# 20_SwitchingRegulator_CH_C-D.net
KiCad netlist of a schematic drawn in Altium Designer
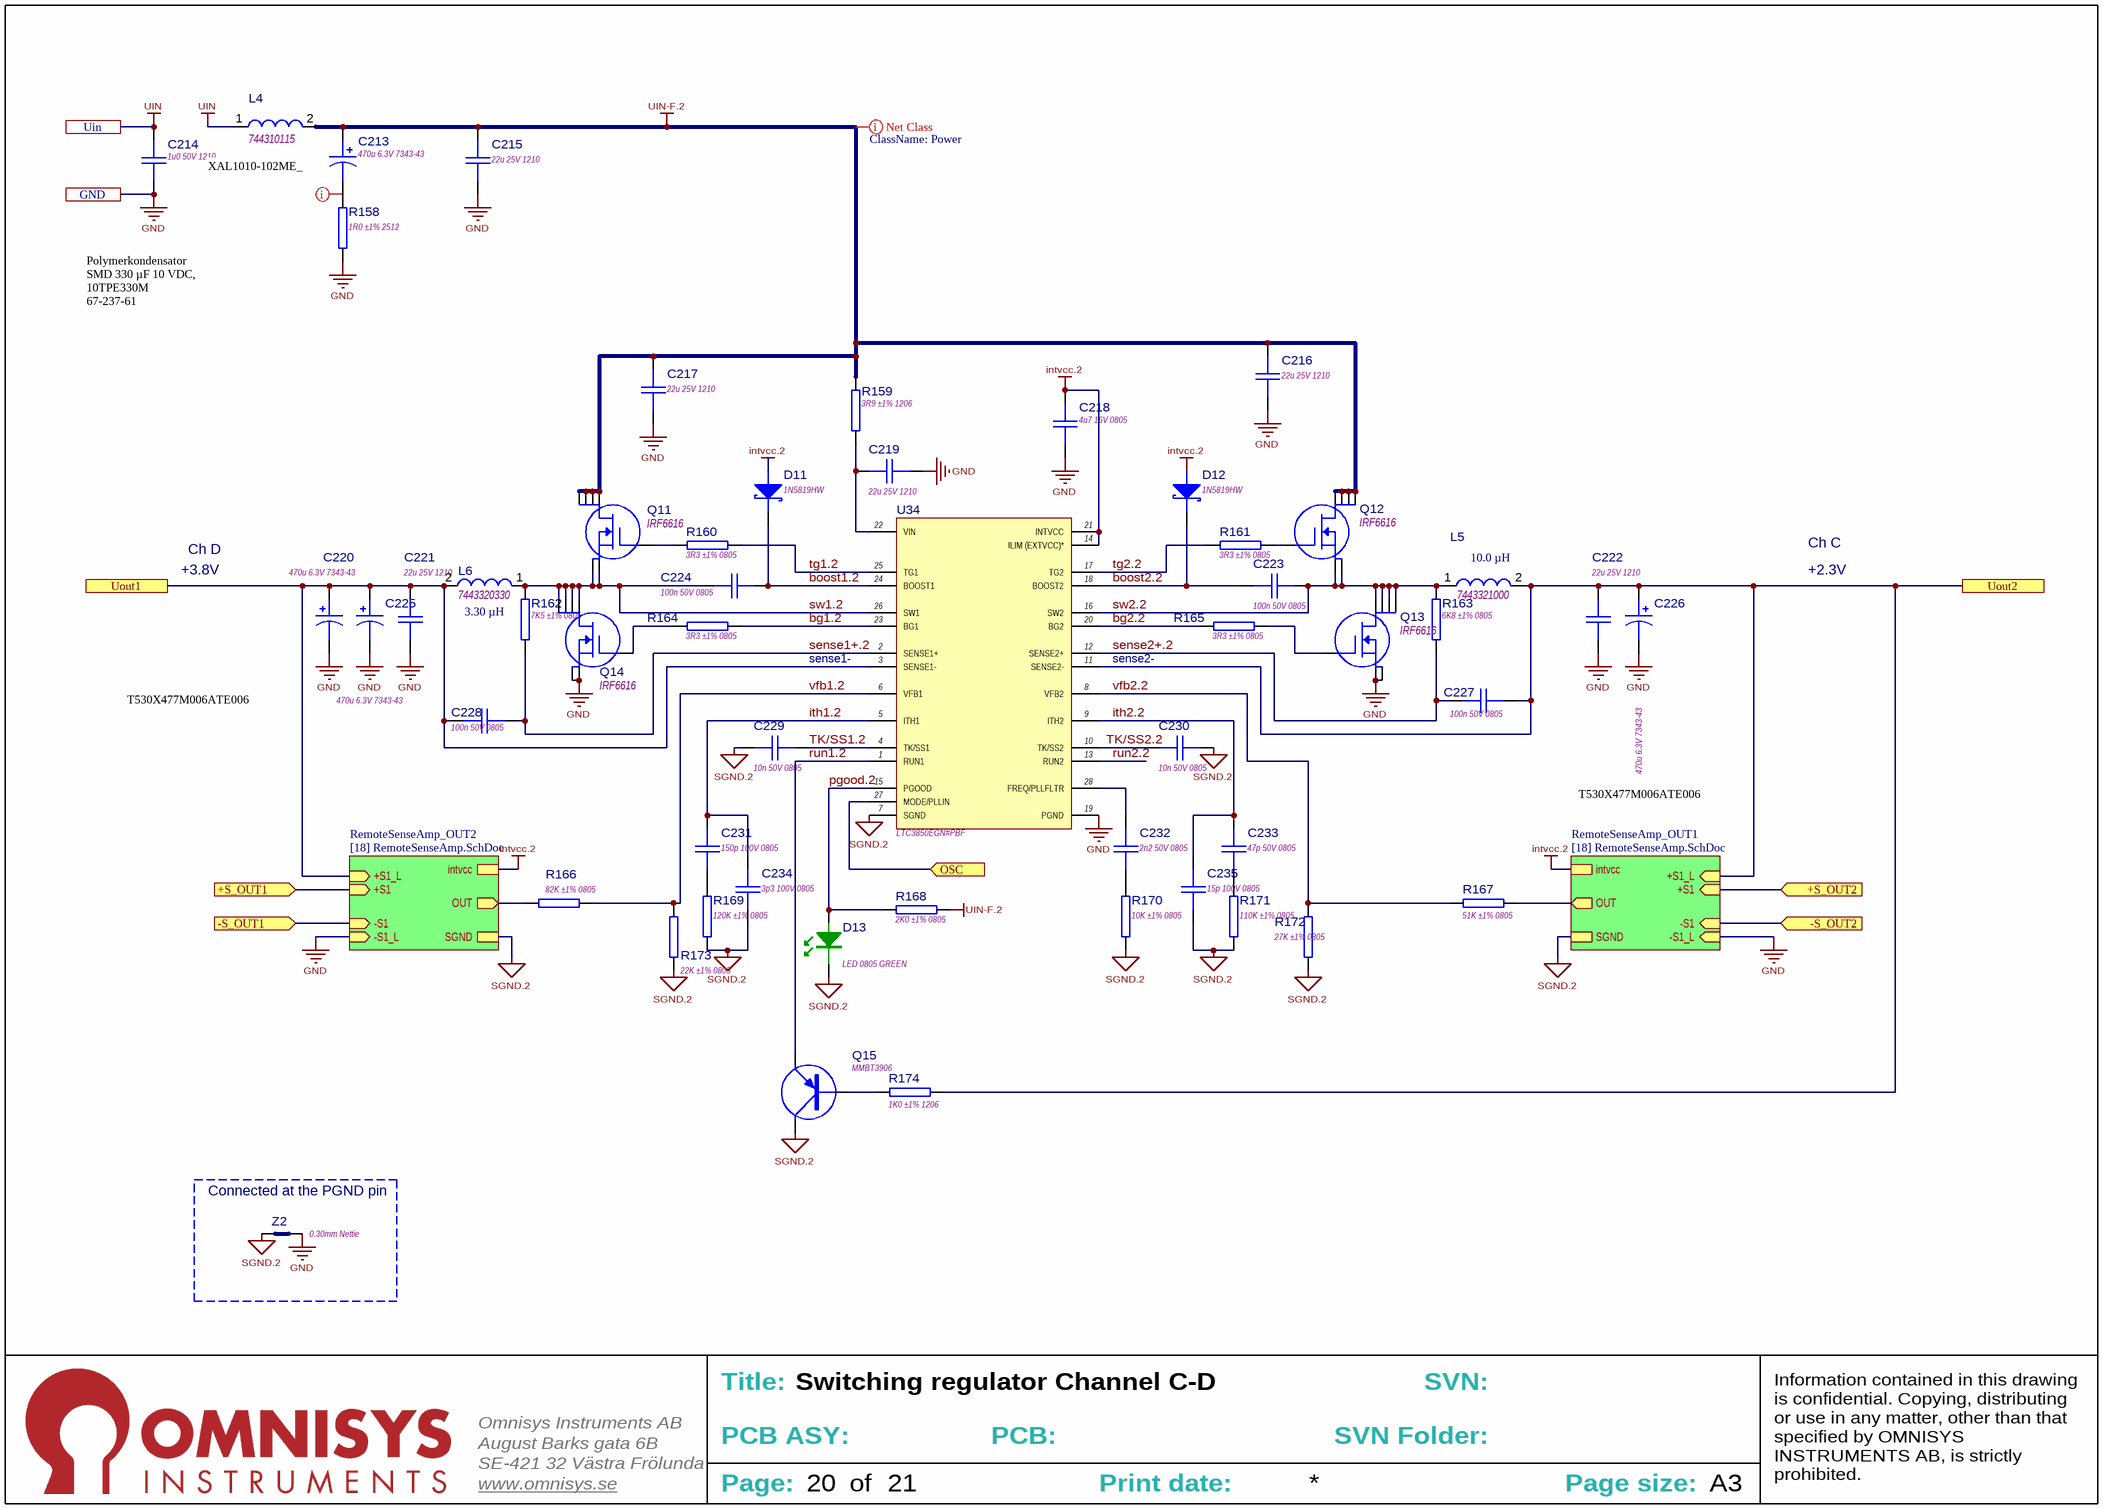
[diagram p0: [20] SwitchingRegulator CH C-D.SchDoc]

(export (version "E")
  (design (tool "Eeschema 10.0.6"))
  (components
    (comp (ref "C213")
      (value "470u 6.3V 7343-43")
      (footprint "CAPMP7343X43N")
      (description "Standard tantalum capacitor, 470u 6.3V 7343-43, Case E, TAJE477M006#NJ")
      (fields (field (name "TOLERANCE") "±20%"))
      (libsource (lib "") (part "CAP-2PIN-POL_1"))
    )
    (comp (ref "C214")
      (value "1u0 50V 1210")
      (footprint "CAPC3225X200N")
      (description "1u0 50V X7R ±10% 1210 (3225 metric)")
      (fields (field (name "TOLERANCE") "10%") (field (name "PARTNUMBER") "GRM32RR71H105KA01"))
      (libsource (lib "Omnisys Vault") (part "CAP-2PIN"))
    )
    (comp (ref "C215")
      (value "22u 25V 1210")
      (footprint "CAPC3225X270N")
      (description "22u 25V X7R ±10% 1210 (3225 metric)")
      (fields (field (name "TOLERANCE") "10%") (field (name "PARTNUMBER") "GRM32ER71E226ME15"))
      (libsource (lib "Omnisys Vault") (part "CAP-2PIN"))
    )
    (comp (ref "C216")
      (value "22u 25V 1210")
      (footprint "CAPC3225X270N")
      (description "22u 25V X7R ±10% 1210 (3225 metric)")
      (fields (field (name "TOLERANCE") "10%") (field (name "PARTNUMBER") "GRM32ER71E226ME15"))
      (libsource (lib "Omnisys Vault") (part "CAP-2PIN"))
    )
    (comp (ref "C217")
      (value "22u 25V 1210")
      (footprint "CAPC3225X270N")
      (description "22u 25V X7R ±10% 1210 (3225 metric)")
      (fields (field (name "TOLERANCE") "10%") (field (name "PARTNUMBER") "GRM32ER71E226ME15"))
      (libsource (lib "Omnisys Vault") (part "CAP-2PIN"))
    )
    (comp (ref "C218")
      (value "4u7 16V 0805")
      (footprint "CAPC2012X140N")
      (description "4u7 16V X7R ±10% 0805 (2012 metric)")
      (fields (field (name "TOLERANCE") "10%") (field (name "PARTNUMBER") "GRM21BR71C475KA73"))
      (libsource (lib "Omnisys Vault") (part "CAP-2PIN"))
    )
    (comp (ref "C219")
      (value "22u 25V 1210")
      (footprint "CAPC3225X270N")
      (description "22u 25V X7R ±10% 1210 (3225 metric)")
      (fields (field (name "TOLERANCE") "10%") (field (name "PARTNUMBER") "GRM32ER71E226ME15"))
      (libsource (lib "Omnisys Vault") (part "CAP-2PIN"))
    )
    (comp (ref "C220")
      (value "470u 6.3V 7343-43")
      (footprint "CAPMP7343X43N")
      (description "Standard tantalum capacitor, 470u 6.3V 7343-43, Case E, TAJE477M006#NJ")
      (fields (field (name "TOLERANCE") "±20%"))
      (libsource (lib "Omnisys Vault") (part "CAP-2PIN-POL"))
    )
    (comp (ref "C221")
      (value "22u 25V 1210")
      (footprint "CAPC3225X270N")
      (description "22u 25V X7R ±10% 1210 (3225 metric)")
      (fields (field (name "TOLERANCE") "10%") (field (name "PARTNUMBER") "GRM32ER71E226ME15"))
      (libsource (lib "Omnisys Vault") (part "CAP-2PIN"))
    )
    (comp (ref "C222")
      (value "22u 25V 1210")
      (footprint "CAPC3225X270N")
      (description "22u 25V X7R ±10% 1210 (3225 metric)")
      (fields (field (name "TOLERANCE") "10%") (field (name "PARTNUMBER") "GRM32ER71E226ME15"))
      (libsource (lib "Omnisys Vault") (part "CAP-2PIN"))
    )
    (comp (ref "C223")
      (value "100n 50V 0805")
      (footprint "CAPC2012X135N")
      (description "100n 50V X7R ±10% 0805 (2012 metric)")
      (fields (field (name "TOLERANCE") "10%") (field (name "PARTNUMBER") "GRM21BR71H104KA01"))
      (libsource (lib "Omnisys Vault") (part "CAP-2PIN"))
    )
    (comp (ref "C224")
      (value "100n 50V 0805")
      (footprint "CAPC2012X135N")
      (description "100n 50V X7R ±10% 0805 (2012 metric)")
      (fields (field (name "TOLERANCE") "10%") (field (name "PARTNUMBER") "GRM21BR71H104KA01"))
      (libsource (lib "Omnisys Vault") (part "CAP-2PIN"))
    )
    (comp (ref "C225")
      (value "470u 6.3V 7343-43")
      (footprint "CAPMP7343X43N")
      (description "Standard tantalum capacitor, 470u 6.3V 7343-43, Case E, TAJE477M006#NJ")
      (fields (field (name "TOLERANCE") "±20%"))
      (libsource (lib "Omnisys Vault") (part "CAP-2PIN-POL"))
    )
    (comp (ref "C226")
      (value "470u 6.3V 7343-43")
      (footprint "CAPMP7343X43N")
      (description "Standard tantalum capacitor, 470u 6.3V 7343-43, Case E, TAJE477M006#NJ")
      (fields (field (name "TOLERANCE") "±20%"))
      (libsource (lib "") (part "CAP-2PIN-POL_1"))
    )
    (comp (ref "C227")
      (value "100n 50V 0805")
      (footprint "CAPC2012X135N")
      (description "100n 50V X7R ±10% 0805 (2012 metric)")
      (fields (field (name "TOLERANCE") "10%") (field (name "PARTNUMBER") "GRM21BR71H104KA01"))
      (libsource (lib "Omnisys Vault") (part "CAP-2PIN"))
    )
    (comp (ref "C228")
      (value "100n 50V 0805")
      (footprint "CAPC2012X135N")
      (description "100n 50V X7R ±10% 0805 (2012 metric)")
      (fields (field (name "TOLERANCE") "10%") (field (name "PARTNUMBER") "GRM21BR71H104KA01"))
      (libsource (lib "Omnisys Vault") (part "CAP-2PIN"))
    )
    (comp (ref "C229")
      (value "10n 50V 0805")
      (footprint "CAPC2012X95L")
      (description "10n 50V X7R ±10% 0805 (2012 metric)")
      (fields (field (name "TOLERANCE") "10%") (field (name "PARTNUMBER") "GRM219R71H103KA01"))
      (libsource (lib "Omnisys Vault") (part "CAP-2PIN"))
    )
    (comp (ref "C230")
      (value "10n 50V 0805")
      (footprint "CAPC2012X95L")
      (description "10n 50V X7R ±10% 0805 (2012 metric)")
      (fields (field (name "TOLERANCE") "10%") (field (name "PARTNUMBER") "GRM219R71H103KA01"))
      (libsource (lib "Omnisys Vault") (part "CAP-2PIN"))
    )
    (comp (ref "C231")
      (value "150p 100V 0805")
      (footprint "CAPC2012X70N")
      (description "150p 100V C0G ±5% 0805 (2012 metric)")
      (fields (field (name "TOLERANCE") "5%") (field (name "PARTNUMBER") "GRM2165C2A151JA01"))
      (libsource (lib "Omnisys Vault") (part "CAP-2PIN"))
    )
    (comp (ref "C232")
      (value "2n2 50V 0805")
      (footprint "CAPC2012X70N")
      (description "2n2 50V C0G ±5% 0805 (2012 metric)")
      (fields (field (name "TOLERANCE") "5%") (field (name "PARTNUMBER") "GRM2165C1H222JA01"))
      (libsource (lib "Omnisys Vault") (part "CAP-2PIN"))
    )
    (comp (ref "C233")
      (value "47p 50V 0805")
      (footprint "CAPC2012X95L")
      (description "47p 50V 0805 C0G +/-5% 0805 (2012 metric)")
      (fields (field (name "TOLERANCE") "5%") (field (name "PARTNUMBER") "GQM2195C1H470JB01"))
      (libsource (lib "Omnisys Vault") (part "CAP-2PIN"))
    )
    (comp (ref "C234")
      (value "3p3 100V 0805")
      (footprint "CAPC2012X95N")
      (description "3p3 100V 0805 C0G +/-0.25pF 0805 (2012 metric)")
      (fields (field (name "TOLERANCE") "5%") (field (name "PARTNUMBER") "GQM2195C2A3R3CB01"))
      (libsource (lib "Omnisys Vault") (part "CAP-2PIN"))
    )
    (comp (ref "C235")
      (value "15p 100V 0805")
      (footprint "CAPC2012X95N")
      (description "15p 100V 0805 C0G +/-5% 0805 (2012 metric)")
      (fields (field (name "TOLERANCE") "5%") (field (name "PARTNUMBER") "GQM2195C2A150JB01"))
      (libsource (lib "Omnisys Vault") (part "CAP-2PIN"))
    )
    (comp (ref "D11")
      (value "1N5819HW")
      (footprint "SOD3716X135L")
      (description "1.0A SURFACE MOUNT SCHOTTKY BARRIER RECTIFIER")
      (libsource (lib "Omnisys Vault") (part "SCHOTTKY-DIODE-2PIN"))
    )
    (comp (ref "D12")
      (value "1N5819HW")
      (footprint "SOD3716X135L")
      (description "1.0A SURFACE MOUNT SCHOTTKY BARRIER RECTIFIER")
      (libsource (lib "Omnisys Vault") (part "SCHOTTKY-DIODE-2PIN"))
    )
    (comp (ref "D13")
      (value "LED 0805 GREEN")
      (footprint "LED2012-GREEN")
      (libsource (lib "Omnisys Vault") (part "LED-2PIN-GREEN"))
    )
    (comp (ref "L4")
      (value "744310115")
      (footprint "WE-HCI-7030")
      (description "SMD Flat Wire High Current Inductor WE-HCI, L=1.15 µH")
      (libsource (lib "Altium Content Vault") (part "PAS-IND-INDUCTOR-2"))
    )
    (comp (ref "L5")
      (value "7443321000")
      (footprint "WE-HCC-1210")
      (description "SMD High Current Cube Inductor WE-HCC, L=10.0 µH")
      (fields (field (name "INDUCTANCE") "10.0 µH"))
      (libsource (lib "Altium Content Vault") (part "CMP-0226-00127-1"))
    )
    (comp (ref "L6")
      (value "7443320330")
      (footprint "WE-HCC-1210")
      (description "SMD High Current Cube Inductor WE-HCC, L=3.30 µH")
      (fields (field (name "INDUCTANCE") "3.30 µH"))
      (libsource (lib "Altium Content Vault") (part "CMP-0226-00120-1"))
    )
    (comp (ref "Q11")
      (value "IRF6616")
      (footprint "DIRECTFET_MX")
      (description "N-Channel MOSFET 40V, 19A, 3.7 mOhm, DirectFET")
      (libsource (lib "Omnisys Vault") (part "IRF6616"))
    )
    (comp (ref "Q12")
      (value "IRF6616")
      (footprint "DIRECTFET_MX")
      (description "N-Channel MOSFET 40V, 19A, 3.7 mOhm, DirectFET")
      (libsource (lib "Omnisys Vault") (part "IRF6616"))
    )
    (comp (ref "Q13")
      (value "IRF6616")
      (footprint "DIRECTFET_MX")
      (description "N-Channel MOSFET 40V, 19A, 3.7 mOhm, DirectFET")
      (libsource (lib "Omnisys Vault") (part "IRF6616"))
    )
    (comp (ref "Q14")
      (value "IRF6616")
      (footprint "DIRECTFET_MX")
      (description "N-Channel MOSFET 40V, 19A, 3.7 mOhm, DirectFET")
      (libsource (lib "Omnisys Vault") (part "IRF6616"))
    )
    (comp (ref "Q15")
      (value "MMBT3906")
      (footprint "SOT95P230X110-3N")
      (description "PNP Bipolar transistor, 40V/0.2A, SOT-23")
      (libsource (lib "Omnisys Vault") (part "PNP-3PIN-SOT23"))
    )
    (comp (ref "R158")
      (value "1R0 ±1% 2512")
      (footprint "RESC6332N")
      (description "1R0 ±1% ±100 ppm/˚C 1W 500V 2512 (6332 metric)")
      (fields (field (name "TOLERANCE") "±1%") (field (name "POWER") "0.10W"))
      (libsource (lib "Omnisys Vault") (part "RES-2PIN"))
    )
    (comp (ref "R159")
      (value "3R9 ±1% 1206")
      (footprint "RESC3216L")
      (description "3R9 ±1% ±100 ppm/˚C 0.25W 200V 1206 (3216 metric)")
      (fields (field (name "TOLERANCE") "1") (field (name "POWER") "0.250W"))
      (libsource (lib "Omnisys Vault") (part "RES-2PIN"))
    )
    (comp (ref "R160")
      (value "3R3 ±1% 0805")
      (footprint "RESC2012N")
      (description "3R3 ±1% ±200 ppm/˚C 0.125W 150V 0805 (2012 metric)")
      (fields (field (name "TOLERANCE") "1%") (field (name "POWER") "125mW"))
      (libsource (lib "Omnisys Vault") (part "RES-2PIN"))
    )
    (comp (ref "R161")
      (value "3R3 ±1% 0805")
      (footprint "RESC2012N")
      (description "3R3 ±1% ±200 ppm/˚C 0.125W 150V 0805 (2012 metric)")
      (fields (field (name "TOLERANCE") "1%") (field (name "POWER") "125mW"))
      (libsource (lib "Omnisys Vault") (part "RES-2PIN"))
    )
    (comp (ref "R162")
      (value "7K5 ±1% 0805")
      (footprint "RESC2012N")
      (description "7K5 ±1% ±100 ppm/˚C 0.125W 150V 0805 (2012 metric)")
      (fields (field (name "TOLERANCE") "1%") (field (name "POWER") "125mW"))
      (libsource (lib "Omnisys Vault") (part "RES-2PIN"))
    )
    (comp (ref "R163")
      (value "6K8 ±1% 0805")
      (footprint "RESC2012N")
      (description "6K8 ±1% ±100 ppm/˚C 0.125W 150V 0805 (2012 metric)")
      (fields (field (name "TOLERANCE") "1%") (field (name "POWER") "125mW"))
      (libsource (lib "Omnisys Vault") (part "RES-2PIN"))
    )
    (comp (ref "R164")
      (value "3R3 ±1% 0805")
      (footprint "RESC2012N")
      (description "3R3 ±1% ±200 ppm/˚C 0.125W 150V 0805 (2012 metric)")
      (fields (field (name "TOLERANCE") "1%") (field (name "POWER") "125mW"))
      (libsource (lib "Omnisys Vault") (part "RES-2PIN"))
    )
    (comp (ref "R165")
      (value "3R3 ±1% 0805")
      (footprint "RESC2012N")
      (description "3R3 ±1% ±200 ppm/˚C 0.125W 150V 0805 (2012 metric)")
      (fields (field (name "TOLERANCE") "1%") (field (name "POWER") "125mW"))
      (libsource (lib "Omnisys Vault") (part "RES-2PIN"))
    )
    (comp (ref "R166")
      (value "82K ±1% 0805")
      (footprint "RESC2012N")
      (description "82K ±1% ±100 ppm/˚C 0.125W 150V 0805 (2012 metric)")
      (fields (field (name "TOLERANCE") "1%") (field (name "POWER") "125mW"))
      (libsource (lib "Omnisys Vault") (part "RES-2PIN"))
    )
    (comp (ref "R167")
      (value "51K ±1% 0805")
      (footprint "RESC2012N")
      (description "51K ±1% ±100 ppm/˚C 0.125W 150V 0805 (2012 metric)")
      (fields (field (name "TOLERANCE") "1%") (field (name "POWER") "125mW"))
      (libsource (lib "Omnisys Vault") (part "RES-2PIN"))
    )
    (comp (ref "R168")
      (value "2K0 ±1% 0805")
      (footprint "RESC2012N")
      (description "2K0 ±1% ±100 ppm/˚C 0.125W 150V 0805 (2012 metric)")
      (fields (field (name "POWER") "125mW") (field (name "TOLERANCE") "1%"))
      (libsource (lib "Omnisys Vault") (part "RES-2PIN"))
    )
    (comp (ref "R169")
      (value "120K ±1% 0805")
      (footprint "RESC2012N")
      (description "120K ±1% ±100 ppm/˚C 0.125W 150V 0805 (2012 metric)")
      (fields (field (name "TOLERANCE") "1%") (field (name "POWER") "125mW"))
      (libsource (lib "Omnisys Vault") (part "RES-2PIN"))
    )
    (comp (ref "R170")
      (value "10K ±1% 0805")
      (footprint "RESC2012N")
      (description "10K ±1% ±100 ppm/˚C 0.125W 150V 0805 (2012 metric)")
      (fields (field (name "TOLERANCE") "1%") (field (name "POWER") "125mW"))
      (libsource (lib "Omnisys Vault") (part "RES-2PIN"))
    )
    (comp (ref "R171")
      (value "110K ±1% 0805")
      (footprint "RESC2012N")
      (description "110K ±1% ±100 ppm/˚C 0.125W 150V 0805 (2012 metric) Thickfilm")
      (fields (field (name "TOLERANCE") "1") (field (name "POWER") "0.125W"))
      (libsource (lib "Omnisys Vault") (part "RES-2PIN"))
    )
    (comp (ref "R172")
      (value "27K ±1% 0805")
      (footprint "RESC2012N")
      (description "27K ±1% ±100 ppm/˚C 0.125W 150V 0805 (2012 metric)")
      (fields (field (name "TOLERANCE") "1%") (field (name "POWER") "125mW"))
      (libsource (lib "Omnisys Vault") (part "RES-2PIN"))
    )
    (comp (ref "R173")
      (value "22K ±1% 0805")
      (footprint "RESC2012N")
      (description "22K ±1% ±100 ppm/˚C 0.125W 150V 0805 (2012 metric)")
      (fields (field (name "TOLERANCE") "1%") (field (name "POWER") "125mW"))
      (libsource (lib "Omnisys Vault") (part "RES-2PIN"))
    )
    (comp (ref "R174")
      (value "1K0 ±1% 1206")
      (footprint "RESC3216N")
      (description "1K0 ±1% ±100 ppm/˚C 0.25W 200V 1206 (3216 metric)")
      (fields (field (name "TOLERANCE") "1") (field (name "POWER") "0.250W"))
      (libsource (lib "Omnisys Vault") (part "RES-2PIN"))
    )
    (comp (ref "U34")
      (value "LTC3850EGN#PBF")
      (footprint "SOP64P600X175-28N")
      (description "Dual, 2-Phase Synchronous Step-Down Switching Controller, LTC3850EGN#PBF")
      (libsource (lib "Omnisys Vault") (part "LTC3850"))
    )
    (comp (ref "Z2")
      (value "0.30mm Nettie")
      (footprint "NETTIE_0.3MM")
      (description "Copper object for merging nets on PCB")
      (libsource (lib "Omnisys Vault") (part "NETTIE"))
    )
  )
  (nets
    (net (code "5") (name "/OSC") (class "Default")
      (node (ref "U34") (pin "27") (pinfunction "MODE/PLLIN_27") (pintype "passive"))
    )
    (net (code "6") (name "/OUT") (class "Default")
      (node (ref "R167") (pin "2") (pinfunction "2_2") (pintype "passive"))
    )
    (net (code "7") (name "/OUT_1") (class "Default")
      (node (ref "R166") (pin "2") (pinfunction "2_2") (pintype "passive"))
    )
    (net (code "8") (name "/TK{slash}SS1.2") (class "Default")
      (node (ref "C229") (pin "1") (pinfunction "1_1") (pintype "passive"))
      (node (ref "U34") (pin "4") (pinfunction "TK/SS1_4") (pintype "passive"))
    )
    (net (code "9") (name "/TK{slash}SS2.2") (class "Default")
      (node (ref "C230") (pin "1") (pinfunction "1_1") (pintype "passive"))
      (node (ref "U34") (pin "10") (pinfunction "TK/SS2_10") (pintype "passive"))
    )
    (net (code "10") (name "/Uout1") (class "Default")
      (node (ref "C220") (pin "1") (pinfunction "1_1") (pintype "passive"))
      (node (ref "C221") (pin "1") (pinfunction "1_1") (pintype "passive"))
      (node (ref "C225") (pin "1") (pinfunction "1_1") (pintype "passive"))
      (node (ref "C228") (pin "2") (pinfunction "2_2") (pintype "passive"))
      (node (ref "L6") (pin "2") (pinfunction "2_2") (pintype "passive"))
      (node (ref "U34") (pin "3") (pinfunction "SENSE1-_3") (pintype "passive"))
    )
    (net (code "11") (name "/Uout2") (class "Default")
      (node (ref "C222") (pin "1") (pinfunction "1_1") (pintype "passive"))
      (node (ref "C226") (pin "1") (pinfunction "1_1") (pintype "passive"))
      (node (ref "C227") (pin "1") (pinfunction "1_1") (pintype "passive"))
      (node (ref "L5") (pin "2") (pinfunction "2_2") (pintype "passive"))
      (node (ref "R174") (pin "1") (pinfunction "1_1") (pintype "passive"))
      (node (ref "U34") (pin "11") (pinfunction "SENSE2-_11") (pintype "passive"))
    )
    (net (code "12") (name "/bg1.2") (class "Default")
      (node (ref "R164") (pin "2") (pinfunction "2_2") (pintype "passive"))
      (node (ref "U34") (pin "23") (pinfunction "BG1_23") (pintype "passive"))
    )
    (net (code "13") (name "/bg2.2") (class "Default")
      (node (ref "R165") (pin "1") (pinfunction "1_1") (pintype "passive"))
      (node (ref "U34") (pin "20") (pinfunction "BG2_20") (pintype "passive"))
    )
    (net (code "14") (name "/boost1.2") (class "Default")
      (node (ref "C224") (pin "2") (pinfunction "2_2") (pintype "passive"))
      (node (ref "D11") (pin "1") (pinfunction "K_1") (pintype "passive"))
      (node (ref "U34") (pin "24") (pinfunction "BOOST1_24") (pintype "passive"))
    )
    (net (code "15") (name "/boost2.2") (class "Default")
      (node (ref "C223") (pin "2") (pinfunction "2_2") (pintype "passive"))
      (node (ref "D12") (pin "1") (pinfunction "K_1") (pintype "passive"))
      (node (ref "U34") (pin "18") (pinfunction "BOOST2_18") (pintype "passive"))
    )
    (net (code "16") (name "/ith1.2") (class "Default")
      (node (ref "C231") (pin "1") (pinfunction "1_1") (pintype "passive"))
      (node (ref "C234") (pin "1") (pinfunction "1_1") (pintype "passive"))
      (node (ref "U34") (pin "5") (pinfunction "ITH1_5") (pintype "passive"))
    )
    (net (code "17") (name "/ith2.2") (class "Default")
      (node (ref "C233") (pin "1") (pinfunction "1_1") (pintype "passive"))
      (node (ref "C235") (pin "1") (pinfunction "1_1") (pintype "passive"))
      (node (ref "U34") (pin "9") (pinfunction "ITH2_9") (pintype "passive"))
    )
    (net (code "18") (name "/pgood.2") (class "Default")
      (node (ref "D13") (pin "2") (pintype "passive"))
      (node (ref "R168") (pin "1") (pinfunction "1_1") (pintype "passive"))
      (node (ref "U34") (pin "15") (pinfunction "PGOOD_15") (pintype "passive"))
    )
    (net (code "19") (name "/run1.2") (class "Default")
      (node (ref "Q15") (pin "2") (pinfunction "e_2") (pintype "passive"))
      (node (ref "U34") (pin "1") (pinfunction "RUN1_1") (pintype "passive"))
    )
    (net (code "20") (name "/run2.2") (class "Default")
      (node (ref "U34") (pin "13") (pinfunction "RUN2_13") (pintype "passive"))
    )
    (net (code "21") (name "/sense1+.2") (class "Default")
      (node (ref "C228") (pin "1") (pinfunction "1_1") (pintype "passive"))
      (node (ref "R162") (pin "2") (pinfunction "2_2") (pintype "passive"))
      (node (ref "U34") (pin "2") (pinfunction "SENSE1+_2") (pintype "passive"))
    )
    (net (code "22") (name "/sense2+.2") (class "Default")
      (node (ref "C227") (pin "2") (pinfunction "2_2") (pintype "passive"))
      (node (ref "R163") (pin "1") (pinfunction "1_1") (pintype "passive"))
      (node (ref "U34") (pin "12") (pinfunction "SENSE2+_12") (pintype "passive"))
    )
    (net (code "23") (name "/sw1.2") (class "Default")
      (node (ref "C224") (pin "1") (pinfunction "1_1") (pintype "passive"))
      (node (ref "L6") (pin "1") (pinfunction "1_1") (pintype "passive"))
      (node (ref "Q11") (pin "S1") (pinfunction "S1_S1") (pintype "passive"))
      (node (ref "Q11") (pin "S2") (pinfunction "S2_S2") (pintype "passive"))
      (node (ref "Q14") (pin "D1") (pinfunction "D1_D1") (pintype "passive"))
      (node (ref "Q14") (pin "D2") (pinfunction "D2_D2") (pintype "passive"))
      (node (ref "Q14") (pin "D3") (pinfunction "D3_D3") (pintype "passive"))
      (node (ref "Q14") (pin "D4") (pinfunction "D4_D4") (pintype "passive"))
      (node (ref "R162") (pin "1") (pinfunction "1_1") (pintype "passive"))
      (node (ref "U34") (pin "26") (pinfunction "SW1_26") (pintype "passive"))
    )
    (net (code "24") (name "/sw2.2") (class "Default")
      (node (ref "C223") (pin "1") (pinfunction "1_1") (pintype "passive"))
      (node (ref "L5") (pin "1") (pinfunction "1_1") (pintype "passive"))
      (node (ref "Q12") (pin "S1") (pinfunction "S1_S1") (pintype "passive"))
      (node (ref "Q12") (pin "S2") (pinfunction "S2_S2") (pintype "passive"))
      (node (ref "Q13") (pin "D1") (pinfunction "D1_D1") (pintype "passive"))
      (node (ref "Q13") (pin "D2") (pinfunction "D2_D2") (pintype "passive"))
      (node (ref "Q13") (pin "D3") (pinfunction "D3_D3") (pintype "passive"))
      (node (ref "Q13") (pin "D4") (pinfunction "D4_D4") (pintype "passive"))
      (node (ref "R163") (pin "2") (pinfunction "2_2") (pintype "passive"))
      (node (ref "U34") (pin "16") (pinfunction "SW2_16") (pintype "passive"))
    )
    (net (code "25") (name "/tg1.2") (class "Default")
      (node (ref "R160") (pin "2") (pinfunction "2_2") (pintype "passive"))
      (node (ref "U34") (pin "25") (pinfunction "TG1_25") (pintype "passive"))
    )
    (net (code "26") (name "/tg2.2") (class "Default")
      (node (ref "R161") (pin "1") (pinfunction "1_1") (pintype "passive"))
      (node (ref "U34") (pin "17") (pinfunction "TG2_17") (pintype "passive"))
    )
    (net (code "27") (name "/vfb1.2") (class "Default")
      (node (ref "R166") (pin "1") (pinfunction "1_1") (pintype "passive"))
      (node (ref "R173") (pin "2") (pinfunction "2_2") (pintype "passive"))
      (node (ref "U34") (pin "6") (pinfunction "VFB1_6") (pintype "passive"))
    )
    (net (code "28") (name "/vfb2.2") (class "Default")
      (node (ref "R167") (pin "1") (pinfunction "1_1") (pintype "passive"))
      (node (ref "R172") (pin "2") (pinfunction "2_2") (pintype "passive"))
      (node (ref "U34") (pin "8") (pinfunction "VFB2_8") (pintype "passive"))
    )
    (net (code "29") (name "GND") (class "Default")
      (node (ref "C214") (pin "1") (pinfunction "1_1") (pintype "passive"))
      (node (ref "C215") (pin "2") (pinfunction "2_2") (pintype "passive"))
      (node (ref "C216") (pin "2") (pinfunction "2_2") (pintype "passive"))
      (node (ref "C217") (pin "2") (pinfunction "2_2") (pintype "passive"))
      (node (ref "C218") (pin "1") (pinfunction "1_1") (pintype "passive"))
      (node (ref "C219") (pin "2") (pinfunction "2_2") (pintype "passive"))
      (node (ref "C220") (pin "2") (pinfunction "2_2") (pintype "passive"))
      (node (ref "C221") (pin "2") (pinfunction "2_2") (pintype "passive"))
      (node (ref "C222") (pin "2") (pinfunction "2_2") (pintype "passive"))
      (node (ref "C225") (pin "2") (pinfunction "2_2") (pintype "passive"))
      (node (ref "C226") (pin "2") (pinfunction "2_2") (pintype "passive"))
      (node (ref "Q13") (pin "S1") (pinfunction "S1_S1") (pintype "passive"))
      (node (ref "Q13") (pin "S2") (pinfunction "S2_S2") (pintype "passive"))
      (node (ref "Q14") (pin "S1") (pinfunction "S1_S1") (pintype "passive"))
      (node (ref "Q14") (pin "S2") (pinfunction "S2_S2") (pintype "passive"))
      (node (ref "R158") (pin "1") (pinfunction "1_1") (pintype "passive"))
      (node (ref "U34") (pin "19") (pinfunction "PGND_19") (pintype "passive"))
      (node (ref "Z2") (pin "2") (pinfunction "2_2") (pintype "passive"))
    )
    (net (code "30") (name "Net-(C213-Pad2)") (class "Default")
      (node (ref "C213") (pin "2") (pinfunction "2_2") (pintype "passive"))
      (node (ref "R158") (pin "2") (pinfunction "2_2") (pintype "passive"))
    )
    (net (code "31") (name "Net-(C231-Pad2)") (class "Default")
      (node (ref "C231") (pin "2") (pinfunction "2_2") (pintype "passive"))
      (node (ref "R169") (pin "1") (pinfunction "1_1") (pintype "passive"))
    )
    (net (code "32") (name "Net-(C232-Pad2)") (class "Default")
      (node (ref "C232") (pin "2") (pinfunction "2_2") (pintype "passive"))
      (node (ref "R170") (pin "1") (pinfunction "1_1") (pintype "passive"))
    )
    (net (code "33") (name "Net-(C233-Pad2)") (class "Default")
      (node (ref "C233") (pin "2") (pinfunction "2_2") (pintype "passive"))
      (node (ref "R171") (pin "1") (pinfunction "1_1") (pintype "passive"))
    )
    (net (code "34") (name "Net-(Q11-PadG)") (class "Default")
      (node (ref "Q11") (pin "G") (pinfunction "G_G") (pintype "passive"))
      (node (ref "R160") (pin "1") (pinfunction "1_1") (pintype "passive"))
    )
    (net (code "35") (name "Net-(Q12-PadG)") (class "Default")
      (node (ref "Q12") (pin "G") (pinfunction "G_G") (pintype "passive"))
      (node (ref "R161") (pin "2") (pinfunction "2_2") (pintype "passive"))
    )
    (net (code "36") (name "Net-(Q13-PadG)") (class "Default")
      (node (ref "Q13") (pin "G") (pinfunction "G_G") (pintype "passive"))
      (node (ref "R165") (pin "2") (pinfunction "2_2") (pintype "passive"))
    )
    (net (code "37") (name "Net-(Q14-PadG)") (class "Default")
      (node (ref "Q14") (pin "G") (pinfunction "G_G") (pintype "passive"))
      (node (ref "R164") (pin "1") (pinfunction "1_1") (pintype "passive"))
    )
    (net (code "38") (name "Net-(Q15-b)") (class "Default")
      (node (ref "Q15") (pin "1") (pinfunction "b_1") (pintype "passive"))
      (node (ref "R174") (pin "2") (pinfunction "2_2") (pintype "passive"))
    )
    (net (code "39") (name "Net-(U34-FREQ{slash}PLLFLTR)") (class "Default")
      (node (ref "C232") (pin "1") (pinfunction "1_1") (pintype "passive"))
      (node (ref "U34") (pin "28") (pinfunction "FREQ/PLLFLTR_28") (pintype "passive"))
    )
    (net (code "40") (name "Net-(U34-VIN)") (class "Default")
      (node (ref "C219") (pin "1") (pinfunction "1_1") (pintype "passive"))
      (node (ref "R159") (pin "1") (pinfunction "1_1") (pintype "passive"))
      (node (ref "U34") (pin "22") (pinfunction "VIN_22") (pintype "passive"))
    )
    (net (code "41") (name "SGND.2") (class "Default")
      (node (ref "C229") (pin "2") (pinfunction "2_2") (pintype "passive"))
      (node (ref "C230") (pin "2") (pinfunction "2_2") (pintype "passive"))
      (node (ref "C234") (pin "2") (pinfunction "2_2") (pintype "passive"))
      (node (ref "C235") (pin "2") (pinfunction "2_2") (pintype "passive"))
      (node (ref "D13") (pin "1") (pintype "passive"))
      (node (ref "Q15") (pin "3") (pinfunction "c_3") (pintype "passive"))
      (node (ref "R169") (pin "2") (pinfunction "2_2") (pintype "passive"))
      (node (ref "R170") (pin "2") (pinfunction "2_2") (pintype "passive"))
      (node (ref "R171") (pin "2") (pinfunction "2_2") (pintype "passive"))
      (node (ref "R172") (pin "1") (pinfunction "1_1") (pintype "passive"))
      (node (ref "R173") (pin "1") (pinfunction "1_1") (pintype "passive"))
      (node (ref "U34") (pin "7") (pinfunction "SGND_7") (pintype "passive"))
      (node (ref "Z2") (pin "1") (pinfunction "1_1") (pintype "passive"))
    )
    (net (code "42") (name "UIN") (class "Default")
      (node (ref "C214") (pin "2") (pinfunction "2_2") (pintype "passive"))
      (node (ref "L4") (pin "1") (pinfunction "1_1") (pintype "passive"))
    )
    (net (code "43") (name "UIN-F.2") (class "Default")
      (node (ref "C213") (pin "1") (pinfunction "1_1") (pintype "passive"))
      (node (ref "C215") (pin "1") (pinfunction "1_1") (pintype "passive"))
      (node (ref "C216") (pin "1") (pinfunction "1_1") (pintype "passive"))
      (node (ref "C217") (pin "1") (pinfunction "1_1") (pintype "passive"))
      (node (ref "L4") (pin "2") (pinfunction "2_2") (pintype "passive"))
      (node (ref "Q11") (pin "D1") (pinfunction "D1_D1") (pintype "passive"))
      (node (ref "Q11") (pin "D2") (pinfunction "D2_D2") (pintype "passive"))
      (node (ref "Q11") (pin "D3") (pinfunction "D3_D3") (pintype "passive"))
      (node (ref "Q11") (pin "D4") (pinfunction "D4_D4") (pintype "passive"))
      (node (ref "Q12") (pin "D1") (pinfunction "D1_D1") (pintype "passive"))
      (node (ref "Q12") (pin "D2") (pinfunction "D2_D2") (pintype "passive"))
      (node (ref "Q12") (pin "D3") (pinfunction "D3_D3") (pintype "passive"))
      (node (ref "Q12") (pin "D4") (pinfunction "D4_D4") (pintype "passive"))
      (node (ref "R159") (pin "2") (pinfunction "2_2") (pintype "passive"))
      (node (ref "R168") (pin "2") (pinfunction "2_2") (pintype "passive"))
    )
    (net (code "44") (name "intvcc.2") (class "Default")
      (node (ref "C218") (pin "2") (pinfunction "2_2") (pintype "passive"))
      (node (ref "D11") (pin "2") (pinfunction "A_2") (pintype "passive"))
      (node (ref "D12") (pin "2") (pinfunction "A_2") (pintype "passive"))
      (node (ref "U34") (pin "14") (pinfunction "ILIM_(EXTVCC)*_14") (pintype "passive"))
      (node (ref "U34") (pin "21") (pinfunction "INTVCC_21") (pintype "passive"))
    )
  )
)
